# soldier_Integrators.net
KiCad netlist of a schematic drawn in Altium Designer
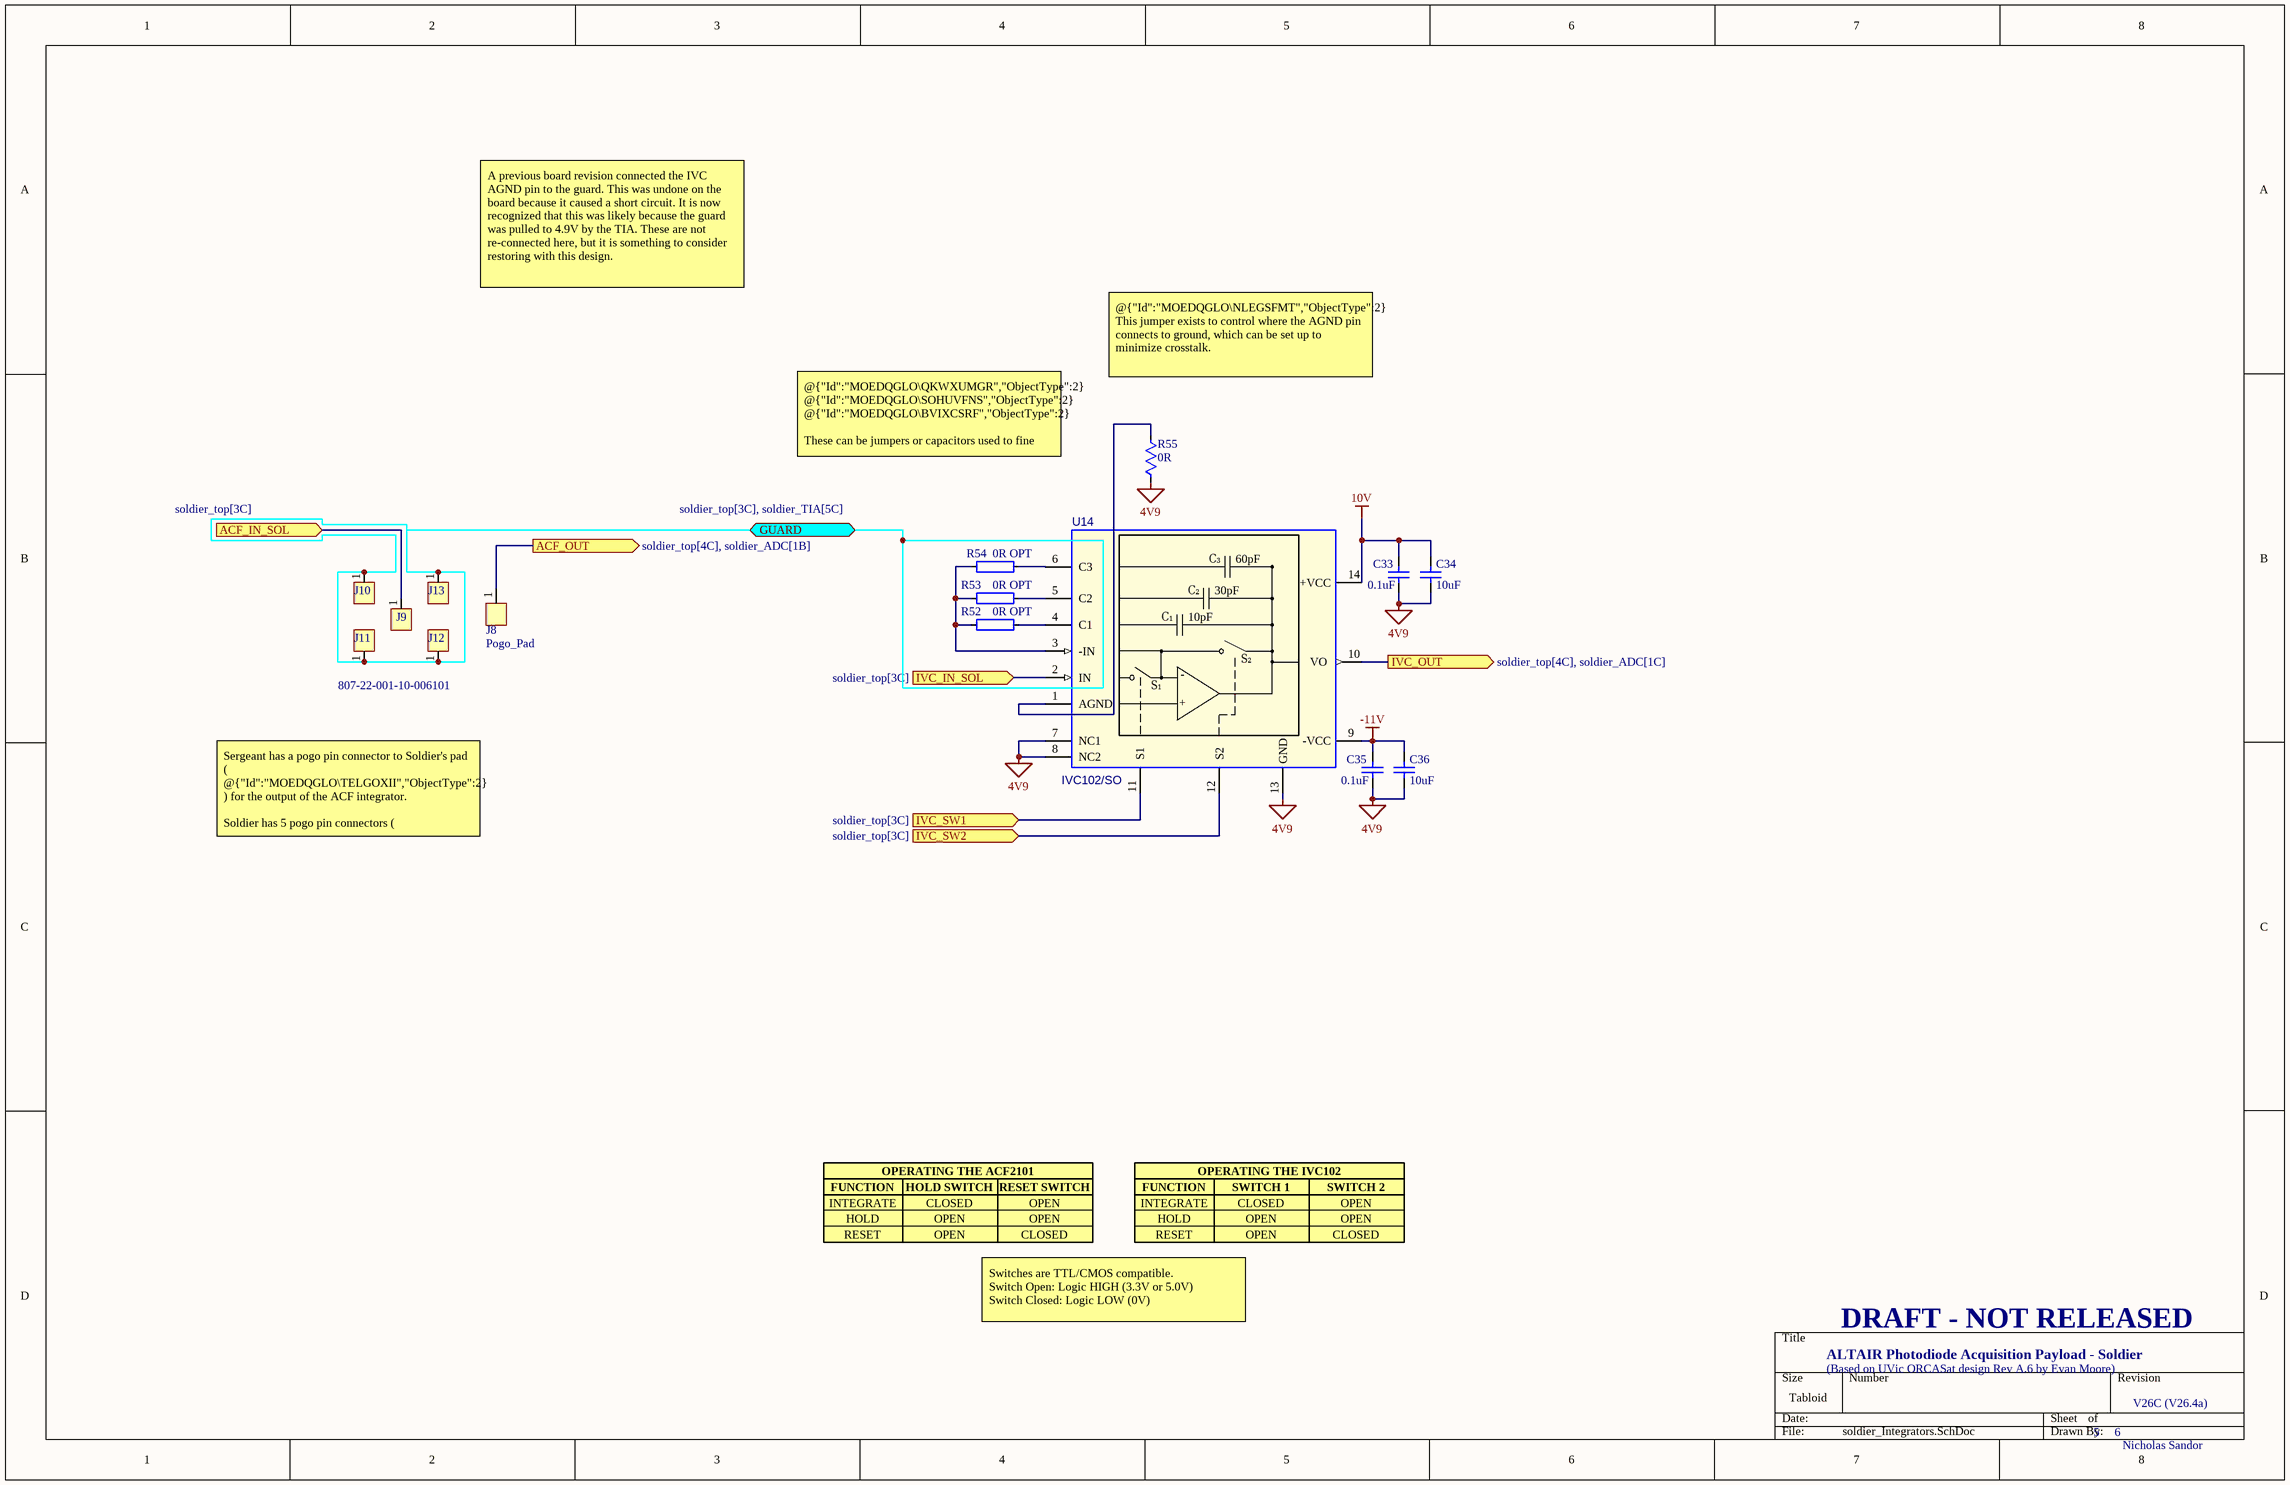
[diagram p0: soldier_Integrators.SchDoc]

(export (version "E")
  (design (tool "Eeschema 10.0.6"))
  (components
    (comp (ref "C33")
      (value "0.1uF")
      (footprint "CAP 0603 NON-IPC KEMET X7R")
      (description "Kemet C0603C104K5RACAUTO - Cap Ceramic 0.1uF 50V X7R 10% 0603 125C Paper T/R")
      (fields (field (name "MF") "Kemet") (field (name "MP") "C0603C104K5RACAUTO"))
      (libsource (lib "ALTAIR_PD_Capacitors") (part "CAP"))
    )
    (comp (ref "C34")
      (value "10uF")
      (footprint "CAP 0805 IPC MID DENSITY")
      (description "Murata GRM21BR61E106KA73L - Cap Ceramic 10uF 10% 25V X5R 0805")
      (fields (field (name "MF") "Murata") (field (name "MP") "GRM21BR61E106KA73L"))
      (libsource (lib "ALTAIR_PD_Capacitors") (part "CAP"))
    )
    (comp (ref "C35")
      (value "0.1uF")
      (footprint "CAP 0603 NON-IPC KEMET X7R")
      (description "Kemet C0603C104K5RACAUTO - Cap Ceramic 0.1uF 50V X7R 10% 0603 125C Paper T/R")
      (fields (field (name "MF") "Kemet") (field (name "MP") "C0603C104K5RACAUTO"))
      (libsource (lib "ALTAIR_PD_Capacitors") (part "CAP"))
    )
    (comp (ref "C36")
      (value "10uF")
      (footprint "CAP 0805 IPC MID DENSITY")
      (description "Murata GRM21BR61E106KA73L - Cap Ceramic 10uF 10% 25V X5R 0805")
      (fields (field (name "MF") "Murata") (field (name "MP") "GRM21BR61E106KA73L"))
      (libsource (lib "ALTAIR_PD_Capacitors") (part "CAP"))
    )
    (comp (ref "J8")
      (value "Pogo_Pad")
      (footprint "POGO PAD SOLDIER")
      (description "Pad for Pogo Pin without Guard")
      (libsource (lib "ALTAIR_PD_Pogo") (part "Pogo_Pad_NoGuard"))
    )
    (comp (ref "J9")
      (value "807-22-001-10-006101")
      (footprint "POGO PIN 807-22-001-10-006101")
      (description "Mill-Max Individual Insulated Pin 5.99mm Initial Height")
      (fields (field (name "MF") "Mill-Max"))
      (libsource (lib "") (part "807-22-001-10-006101_1"))
    )
    (comp (ref "J10")
      (value "807-22-001-10-006101")
      (footprint "POGO PIN 807-22-001-10-006101")
      (description "Mill-Max Individual Insulated Pin 5.99mm Initial Height")
      (fields (field (name "MF") "Mill-Max"))
      (libsource (lib "") (part "807-22-001-10-006101_1"))
    )
    (comp (ref "J11")
      (value "807-22-001-10-006101")
      (footprint "POGO PIN 807-22-001-10-006101")
      (description "Mill-Max Individual Insulated Pin 5.99mm Initial Height")
      (fields (field (name "MF") "Mill-Max"))
      (libsource (lib "ALTAIR_PD_Pogo") (part "807-22-001-10-006101"))
    )
    (comp (ref "J12")
      (value "807-22-001-10-006101")
      (footprint "POGO PIN 807-22-001-10-006101")
      (description "Mill-Max Individual Insulated Pin 5.99mm Initial Height")
      (fields (field (name "MF") "Mill-Max"))
      (libsource (lib "ALTAIR_PD_Pogo") (part "807-22-001-10-006101"))
    )
    (comp (ref "J13")
      (value "807-22-001-10-006101")
      (footprint "POGO PIN 807-22-001-10-006101")
      (description "Mill-Max Individual Insulated Pin 5.99mm Initial Height")
      (fields (field (name "MF") "Mill-Max"))
      (libsource (lib "") (part "807-22-001-10-006101_1"))
    )
    (comp (ref "R52")
      (value "0R OPT")
      (footprint "RES 0402 IPC LOW DENSITY")
      (description "Yageo RC0402JR-070RL - Res 0 Ohms 1/16W SMD 0402")
      (fields (field (name "MF") "YAGEO") (field (name "MP") "RC0402JR-070RL"))
      (libsource (lib "ALTAIR_PD_Resistors") (part "IMPEDANCE"))
    )
    (comp (ref "R53")
      (value "0R OPT")
      (footprint "RES 0402 IPC LOW DENSITY")
      (description "Yageo RC0402JR-070RL - Res 0 Ohms 1/16W SMD 0402")
      (fields (field (name "MF") "YAGEO") (field (name "MP") "RC0402JR-070RL"))
      (libsource (lib "ALTAIR_PD_Resistors") (part "IMPEDANCE"))
    )
    (comp (ref "R54")
      (value "0R OPT")
      (footprint "RES 0402 IPC LOW DENSITY")
      (description "Yageo RC0402JR-070RL - Res 0 Ohms 1/16W SMD 0402")
      (fields (field (name "MF") "YAGEO") (field (name "MP") "RC0402JR-070RL"))
      (libsource (lib "ALTAIR_PD_Resistors") (part "IMPEDANCE"))
    )
    (comp (ref "R55")
      (value "0R")
      (footprint "RES 0402 IPC MID DENSITY")
      (description "Yageo RC0402JR-070RL - Res 0 Ohms 1/16W SMD 0402")
      (fields (field (name "MF") "YAGEO") (field (name "MP") "RC0402JR-070RL"))
      (libsource (lib "ALTAIR_PD_Resistors") (part "RES"))
    )
    (comp (ref "U14")
      (value "IVC102/SO")
      (footprint "14-SOIC 4MM WIDE LOW DENSITY")
      (description "Precision Switched Integrator Transimpedance Amplifier")
      (fields (field (name "MF") "Texas Instruments"))
      (libsource (lib "ALTAIR_PD_Amplifiers") (part "IVC102/SO_5"))
    )
  )
  (nets
    (net (code "1") (name "-11V") (class "Default")
      (node (ref "C35") (pin "2") (pinfunction "2_2") (pintype "passive"))
      (node (ref "C36") (pin "2") (pinfunction "2_2") (pintype "passive"))
      (node (ref "U14") (pin "9") (pinfunction "-VCC_9") (pintype "power_in"))
    )
    (net (code "2") (name "/ACF_IN_SOL") (class "Default")
      (node (ref "J9") (pin "1") (pinfunction "1_1") (pintype "passive"))
    )
    (net (code "3") (name "/ACF_OUT") (class "Default")
      (node (ref "J8") (pin "1") (pinfunction "1_1") (pintype "passive"))
    )
    (net (code "4") (name "/GUARD") (class "Default")
      (node (ref "J10") (pin "1") (pinfunction "1_1") (pintype "passive"))
      (node (ref "J11") (pin "1") (pinfunction "1_1") (pintype "passive"))
      (node (ref "J12") (pin "1") (pinfunction "1_1") (pintype "passive"))
      (node (ref "J13") (pin "1") (pinfunction "1_1") (pintype "passive"))
    )
    (net (code "5") (name "/IVC_IN_SOL") (class "Default")
      (node (ref "U14") (pin "2") (pinfunction "IN_2") (pintype "input"))
    )
    (net (code "6") (name "/IVC_OUT") (class "Default")
      (node (ref "U14") (pin "10") (pinfunction "VO_10") (pintype "output"))
    )
    (net (code "7") (name "/IVC_SW1") (class "Default")
      (node (ref "U14") (pin "11") (pinfunction "S1_11") (pintype "passive"))
    )
    (net (code "8") (name "/IVC_SW2") (class "Default")
      (node (ref "U14") (pin "12") (pinfunction "S2_12") (pintype "passive"))
    )
    (net (code "9") (name "4V9") (class "Default")
      (node (ref "C33") (pin "1") (pinfunction "1_1") (pintype "passive"))
      (node (ref "C34") (pin "1") (pinfunction "1_1") (pintype "passive"))
      (node (ref "C35") (pin "1") (pinfunction "1_1") (pintype "passive"))
      (node (ref "C36") (pin "1") (pinfunction "1_1") (pintype "passive"))
      (node (ref "R55") (pin "2") (pinfunction "2_2") (pintype "passive"))
      (node (ref "U14") (pin "13") (pinfunction "GND_13") (pintype "power_in"))
      (node (ref "U14") (pin "7") (pinfunction "NC1_7") (pintype "passive"))
      (node (ref "U14") (pin "8") (pinfunction "NC2_8") (pintype "passive"))
    )
    (net (code "10") (name "10V") (class "Default")
      (node (ref "C33") (pin "2") (pinfunction "2_2") (pintype "passive"))
      (node (ref "C34") (pin "2") (pinfunction "2_2") (pintype "passive"))
      (node (ref "U14") (pin "14") (pinfunction "+VCC_14") (pintype "power_in"))
    )
    (net (code "11") (name "Net-(U14--IN)") (class "Default")
      (node (ref "R52") (pin "1") (pinfunction "1_1") (pintype "passive"))
      (node (ref "R53") (pin "1") (pinfunction "1_1") (pintype "passive"))
      (node (ref "R54") (pin "1") (pinfunction "1_1") (pintype "passive"))
      (node (ref "U14") (pin "3") (pinfunction "-IN_3") (pintype "input"))
    )
    (net (code "12") (name "Net-(U14-AGND)") (class "Default")
      (node (ref "R55") (pin "1") (pinfunction "1_1") (pintype "passive"))
      (node (ref "U14") (pin "1") (pinfunction "AGND_1") (pintype "power_in"))
    )
    (net (code "13") (name "Net-(U14-C1)") (class "Default")
      (node (ref "R52") (pin "2") (pinfunction "2_2") (pintype "passive"))
      (node (ref "U14") (pin "4") (pinfunction "C1_4") (pintype "passive"))
    )
    (net (code "14") (name "Net-(U14-C2)") (class "Default")
      (node (ref "R53") (pin "2") (pinfunction "2_2") (pintype "passive"))
      (node (ref "U14") (pin "5") (pinfunction "C2_5") (pintype "passive"))
    )
    (net (code "15") (name "Net-(U14-C3)") (class "Default")
      (node (ref "R54") (pin "2") (pinfunction "2_2") (pintype "passive"))
      (node (ref "U14") (pin "6") (pinfunction "C3_6") (pintype "passive"))
    )
  )
)
